# BattCharging_Sheet.net
KiCad netlist of a schematic drawn in Altium Designer
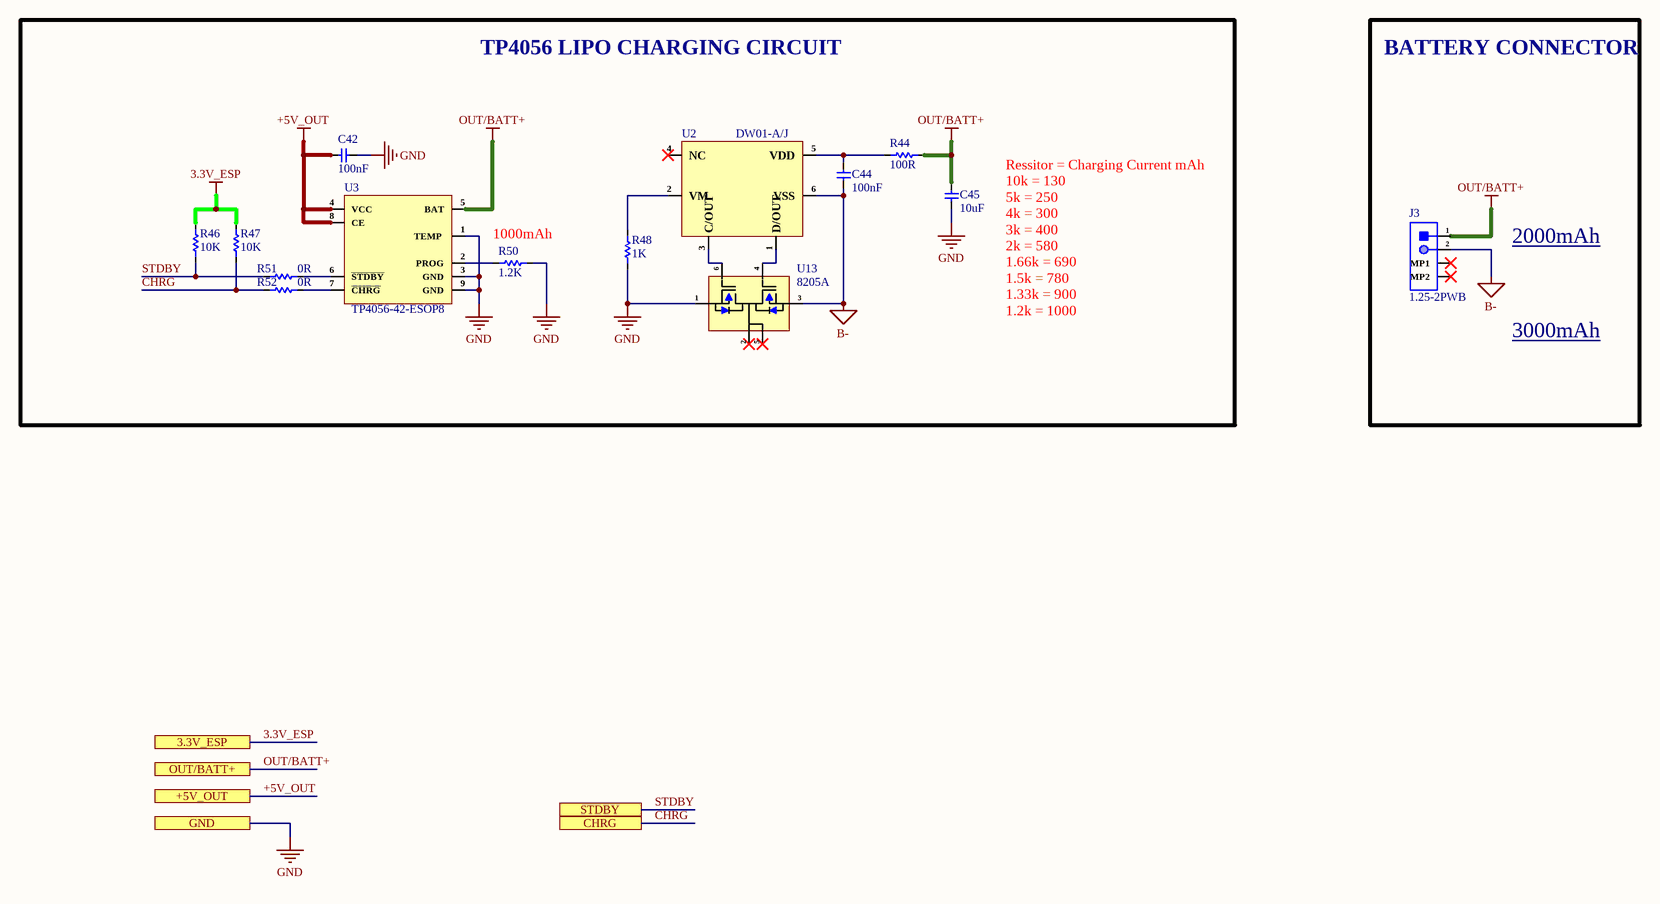
[diagram p0: BattCharging_Sheet.SchDoc]

(export (version "E")
  (design (tool "Eeschema 10.0.6"))
  (components
    (comp (ref "C42")
      (value "100nF")
      (footprint "cap-0402")
      (description "CAP CER 0.1UF 50V X7R 0402")
      (fields
        (field (name "MANUFACTURER") "TDK")
        (field (name "MANUFACTURER PART NUMBER") "C1005X7R1H104KT000F")
      )
      (libsource (lib "eSpark Libraries") (part "C1005X7R1H104KT000F"))
    )
    (comp (ref "C44")
      (value "100nF")
      (footprint "cap-0402")
      (description "CAP CER 0.1UF 50V X7R 0402")
      (fields
        (field (name "MANUFACTURER") "TDK")
        (field (name "MANUFACTURER PART NUMBER") "C1005X7R1H104KT000F")
      )
      (libsource (lib "eSpark Libraries") (part "C1005X7R1H104KT000F"))
    )
    (comp (ref "C45")
      (value "10uF")
      (footprint "Cap-0402")
      (description "CAP CER 10UF 10V X5R 0402")
      (fields
        (field (name "MANUFACTURER") "Samsung")
        (field (name "MANUFACTURER PART NUMBER") "CL05A106MP5NUNC")
      )
      (libsource (lib "eSpark Libraries") (part "CL05A106MP5NUNC"))
    )
    (comp (ref "J3")
      (value "1.25-2PWB")
      (footprint "1.25-2PWB")
      (fields (field (name "MANUFACTURER") "DEALON") (field (name "LCSC PART NUMBER") "C2905009"))
      (libsource (lib "eSpark Libraries") (part "1.25-2PWB"))
    )
    (comp (ref "R44")
      (value "100R")
      (footprint "RES-0805")
      (description "RES SMD 100 OHM 1% 1/8W 0805")
      (fields
        (field (name "MANUFACTURER") "Yageo")
        (field (name "MANUFACTURER PART NUMBER") "AC0805FR-07100RL")
      )
      (libsource (lib "eSpark Libraries") (part "AC0805FR-07100RL"))
    )
    (comp (ref "R46")
      (value "10K")
      (footprint "Res-0402")
      (description "RES 10K OHM 1% 1/16W 0402")
      (fields
        (field (name "MANUFACTURER") "Yageo")
        (field (name "MANUFACTURER PART NUMBER") "RC0402FR-0710KL")
      )
      (libsource (lib "eSpark Libraries") (part "RC0402FR-0710KL"))
    )
    (comp (ref "R47")
      (value "10K")
      (footprint "Res-0402")
      (description "RES 10K OHM 1% 1/16W 0402")
      (fields
        (field (name "MANUFACTURER") "Yageo")
        (field (name "MANUFACTURER PART NUMBER") "RC0402FR-0710KL")
      )
      (libsource (lib "eSpark Libraries") (part "RC0402FR-0710KL"))
    )
    (comp (ref "R48")
      (value "1K")
      (footprint "Res-0402")
      (description "RES SMD 1K OHM 1% 1/5W 0402")
      (fields
        (field (name "MANUFACTURER") "Vishay Dale")
        (field (name "MANUFACTURER PART NUMBER") "CRCW04021K00FKEDHP")
      )
      (libsource (lib "eSpark Libraries") (part "CRCW04021K00FKEDHP"))
    )
    (comp (ref "R50")
      (value "1.2K")
      (footprint "Res-0402")
      (description "RES 1.2K OHM 1% 1/16W 0402")
      (fields
        (field (name "MANUFACTURER") "Yageo")
        (field (name "MANUFACTURER PART NUMBER") "RC0402FR-071K2L")
      )
      (libsource (lib "eSpark Libraries") (part "RC0402FR-071K2L"))
    )
    (comp (ref "R51")
      (value "0R")
      (footprint "Res-0402")
      (description "RES 0 OHM JUMPER 1/16W 0402")
      (fields
        (field (name "MANUFACTURER") "Yageo")
        (field (name "MANUFACTURER PART NUMBER") "RC0402FR-070RL")
      )
      (libsource (lib "eSpark Libraries") (part "RC0402FR-070RL"))
    )
    (comp (ref "R52")
      (value "0R")
      (footprint "Res-0402")
      (description "RES 0 OHM JUMPER 1/16W 0402")
      (fields
        (field (name "MANUFACTURER") "Yageo")
        (field (name "MANUFACTURER PART NUMBER") "RC0402FR-070RL")
      )
      (libsource (lib "eSpark Libraries") (part "RC0402FR-070RL"))
    )
    (comp (ref "U2")
      (value "DW01-A/J")
      (footprint "SOT-23-6")
      (description "SOT-23-6 Battery Management ROHS")
      (fields
        (field (name "MANUFACTURER") "Shenzhen Fuman Elec")
        (field (name "LCSC PART NUMBER") "C2909013")
      )
      (libsource (lib "eSpark Libraries") (part "DW01-A/J"))
    )
    (comp (ref "U3")
      (value "TP4056-42-ESOP8")
      (footprint "ESOP-8")
      (description "ESOP-8 Battery Management ICs ROHS")
      (fields (field (name "MANUFACTURER") "TOPPOWER") (field (name "LCSC PART NUMBER") "C16581"))
      (libsource (lib "eSpark Libraries") (part "TP4056-42-ESOP8"))
    )
    (comp (ref "U13")
      (value "8205A")
      (footprint "SOT-23-6")
      (description "20V 5A 36mΩ@2.5V,3A 830mW 1.2V@250uA 2 N-Channel SOT-23-6 MOSFETs ROHS")
      (fields (field (name "MANUFACTURER") "UMW") (field (name "LCSC PART NUMBER") "C351449"))
      (libsource (lib "eSpark Libraries") (part "8205A"))
    )
  )
  (nets
    (net (code "1") (name "+5V_OUT") (class "Default")
      (node (ref "C42") (pin "1") (pinfunction "1_1") (pintype "passive"))
      (node (ref "U3") (pin "4") (pinfunction "VCC_4") (pintype "passive"))
      (node (ref "U3") (pin "8") (pinfunction "CE_8") (pintype "passive"))
    )
    (net (code "2") (name "/CHRG") (class "Default")
      (node (ref "R47") (pin "1") (pinfunction "1_1") (pintype "passive"))
      (node (ref "R52") (pin "1") (pinfunction "1_1") (pintype "passive"))
    )
    (net (code "3") (name "/STDBY") (class "Default")
      (node (ref "R46") (pin "1") (pinfunction "1_1") (pintype "passive"))
      (node (ref "R51") (pin "1") (pinfunction "1_1") (pintype "passive"))
    )
    (net (code "4") (name "3.3V_ESP") (class "Default")
      (node (ref "R46") (pin "2") (pinfunction "2_2") (pintype "passive"))
      (node (ref "R47") (pin "2") (pinfunction "2_2") (pintype "passive"))
    )
    (net (code "5") (name "B-") (class "Default")
      (node (ref "C44") (pin "2") (pinfunction "2_2") (pintype "passive"))
      (node (ref "J3") (pin "2") (pinfunction "2_2") (pintype "passive"))
      (node (ref "U13") (pin "3") (pinfunction "S2_3") (pintype "passive"))
      (node (ref "U2") (pin "6") (pinfunction "VSS_6") (pintype "passive"))
    )
    (net (code "6") (name "GND") (class "Default")
      (node (ref "C42") (pin "2") (pinfunction "2_2") (pintype "passive"))
      (node (ref "C45") (pin "1") (pinfunction "1_1") (pintype "passive"))
      (node (ref "R48") (pin "1") (pinfunction "1_1") (pintype "passive"))
      (node (ref "R50") (pin "2") (pinfunction "2_2") (pintype "passive"))
      (node (ref "U13") (pin "1") (pinfunction "S1_1") (pintype "passive"))
      (node (ref "U3") (pin "1") (pinfunction "TEMP_1") (pintype "passive"))
      (node (ref "U3") (pin "3") (pinfunction "GND_3") (pintype "passive"))
      (node (ref "U3") (pin "9") (pinfunction "GND_9") (pintype "passive"))
    )
    (net (code "7") (name "Net-(U2-VDD)") (class "Default")
      (node (ref "C44") (pin "1") (pinfunction "1_1") (pintype "passive"))
      (node (ref "R44") (pin "1") (pinfunction "1_1") (pintype "passive"))
      (node (ref "U2") (pin "5") (pinfunction "VDD_5") (pintype "passive"))
    )
    (net (code "8") (name "Net-(U2-VM)") (class "Default")
      (node (ref "R48") (pin "2") (pinfunction "2_2") (pintype "passive"))
      (node (ref "U2") (pin "2") (pinfunction "VM_2") (pintype "passive"))
    )
    (net (code "9") (name "Net-(U3-PROG)") (class "Default")
      (node (ref "R50") (pin "1") (pinfunction "1_1") (pintype "passive"))
      (node (ref "U3") (pin "2") (pinfunction "PROG_2") (pintype "passive"))
    )
    (net (code "10") (name "Net-(U3-~{CHRG})") (class "Default")
      (node (ref "R52") (pin "2") (pinfunction "2_2") (pintype "passive"))
      (node (ref "U3") (pin "7") (pinfunction "~{CHRG}_7") (pintype "passive"))
    )
    (net (code "11") (name "Net-(U3-~{STDBY})") (class "Default")
      (node (ref "R51") (pin "2") (pinfunction "2_2") (pintype "passive"))
      (node (ref "U3") (pin "6") (pinfunction "~{STDBY}_6") (pintype "passive"))
    )
    (net (code "12") (name "Net-(U13-G1)") (class "Default")
      (node (ref "U13") (pin "6") (pinfunction "G1_6") (pintype "passive"))
      (node (ref "U2") (pin "3") (pinfunction "C/OUT_3") (pintype "passive"))
    )
    (net (code "13") (name "Net-(U13-G2)") (class "Default")
      (node (ref "U13") (pin "4") (pinfunction "G2_4") (pintype "passive"))
      (node (ref "U2") (pin "1") (pinfunction "D/OUT_1") (pintype "passive"))
    )
    (net (code "14") (name "OUT{slash}BATT+") (class "Default")
      (node (ref "C45") (pin "2") (pinfunction "2_2") (pintype "passive"))
      (node (ref "J3") (pin "1") (pinfunction "1_1") (pintype "passive"))
      (node (ref "R44") (pin "2") (pinfunction "2_2") (pintype "passive"))
      (node (ref "U3") (pin "5") (pinfunction "BAT_5") (pintype "passive"))
    )
    (net (code "15") (name "unconnected-(J3-PadMP1)") (class "Default")
      (node (ref "J3") (pin "MP1") (pinfunction "MP1_MP1") (pintype "passive+no_connect"))
    )
    (net (code "16") (name "unconnected-(J3-PadMP2)") (class "Default")
      (node (ref "J3") (pin "MP2") (pinfunction "MP2_MP2") (pintype "passive+no_connect"))
    )
    (net (code "17") (name "unconnected-(U2-NC-Pad4)") (class "Default")
      (node (ref "U2") (pin "4") (pinfunction "NC_4") (pintype "passive+no_connect"))
    )
    (net (code "18") (name "unconnected-(U13-D-Pad2)") (class "Default")
      (node (ref "U13") (pin "2") (pinfunction "D_2") (pintype "passive+no_connect"))
    )
    (net (code "19") (name "unconnected-(U13-D-Pad5)") (class "Default")
      (node (ref "U13") (pin "5") (pinfunction "D_5") (pintype "passive+no_connect"))
    )
  )
)
